# demo_dermis_main_testboard_ibias.net
KiCad netlist of a schematic drawn in Altium Designer
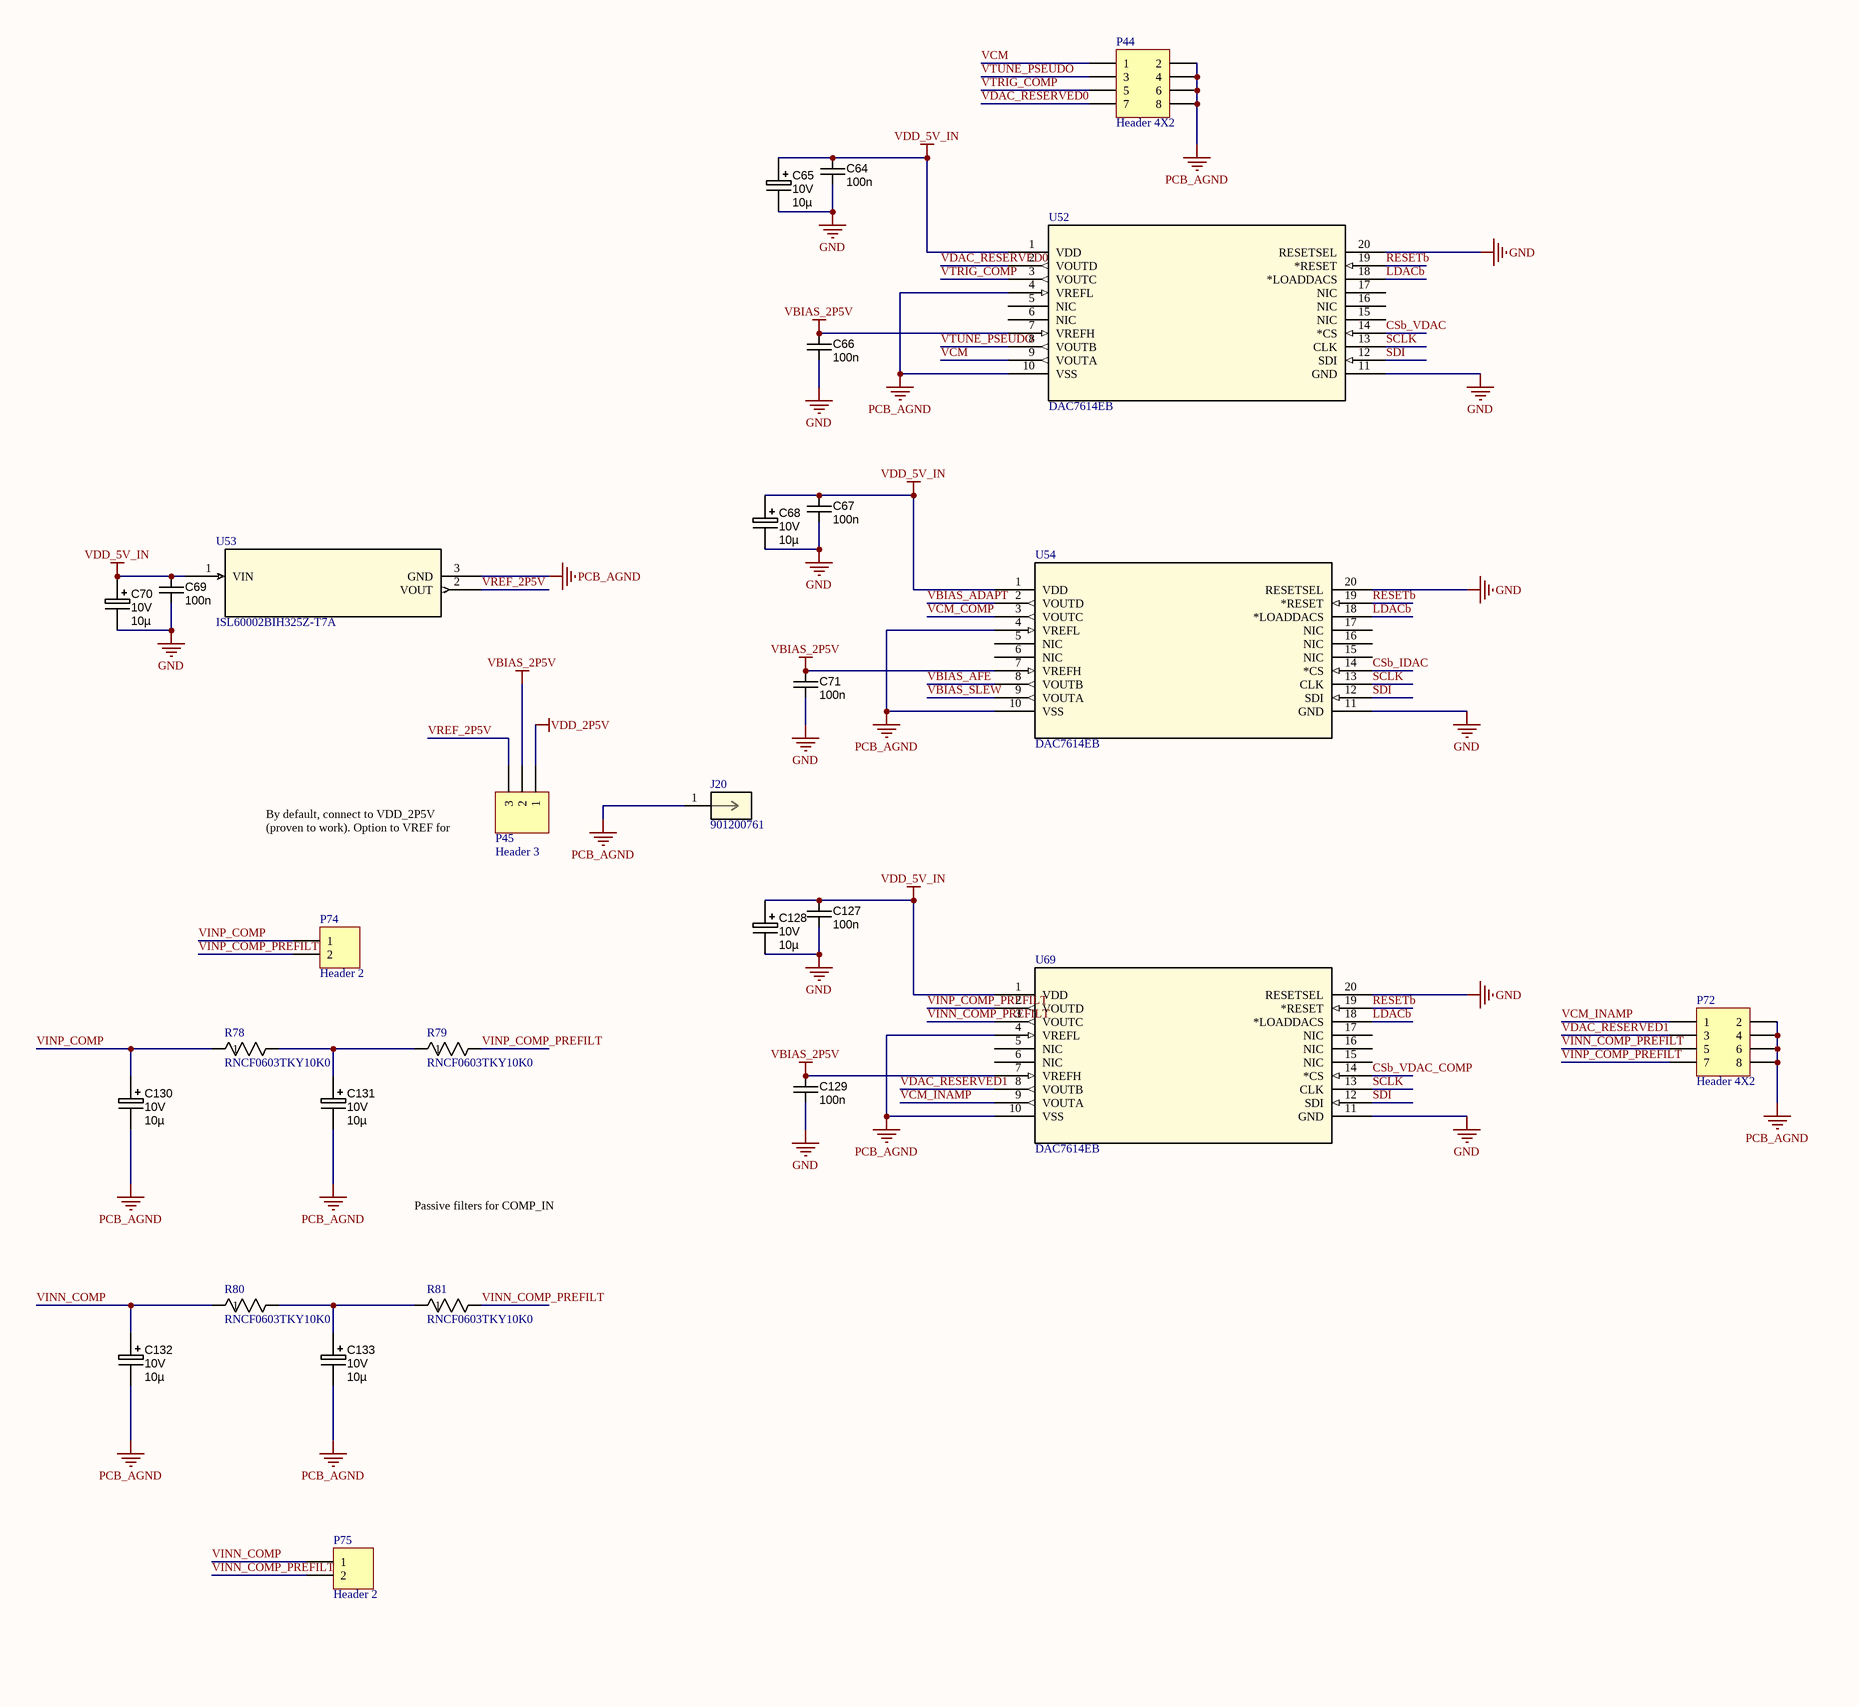
[diagram p0: demo_dermis_main_testboard_ibias.SchDoc, top]
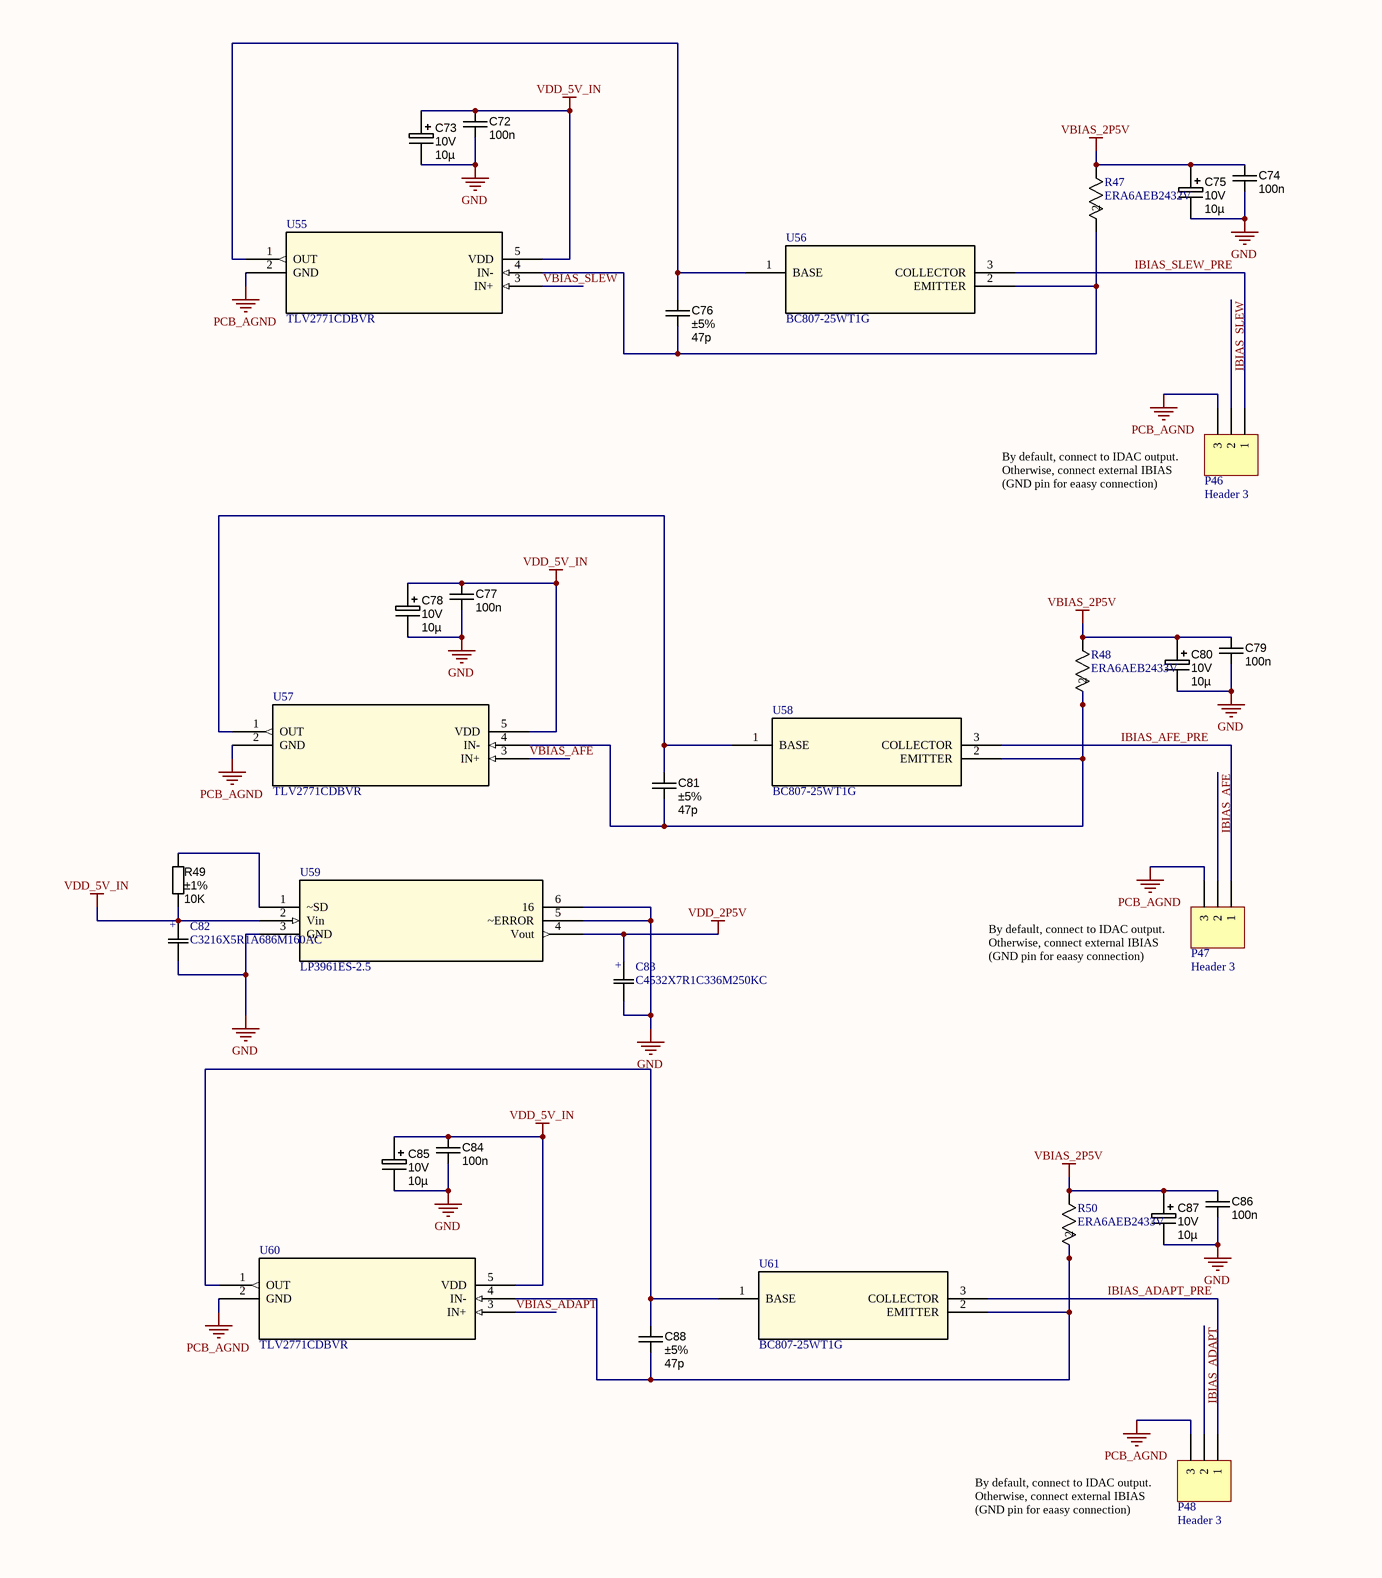
[diagram p1: demo_dermis_main_testboard_ibias.SchDoc, bottom]

(export (version "E")
  (design (tool "Eeschema 10.0.6"))
  (components
    (comp (ref "C64")
      (value "100n")
      (footprint "CAPC1608N")
      (description "Capacitor SMD Cer 100nF 10% 50V X7R 0603")
      (fields (field (name "TOLERANCE") "±10%") (field (name "Comment") "approved sub OK"))
      (libsource (lib "PBL - Capacitors") (part "CAPC_100n_0603"))
    )
    (comp (ref "C65")
      (value "10µ")
      (footprint "CAPMP2012X150USR")
      (description "Capacitor SMD Tantalum 10uF 20% 10V 0805")
      (fields (field (name "TOLERANCE") "±20%") (field (name "RATINGS") "10V"))
      (libsource (lib "PBL - Capacitors") (part "CAPT_10u_0805_10V"))
    )
    (comp (ref "C66")
      (value "100n")
      (footprint "CAPC1608N")
      (description "Capacitor SMD Cer 100nF 10% 50V X7R 0603")
      (fields (field (name "TOLERANCE") "±10%") (field (name "Comment") "approved sub OK"))
      (libsource (lib "PBL - Capacitors") (part "CAPC_100n_0603"))
    )
    (comp (ref "C67")
      (value "100n")
      (footprint "CAPC1608N")
      (description "Capacitor SMD Cer 100nF 10% 50V X7R 0603")
      (fields (field (name "TOLERANCE") "±10%") (field (name "Comment") "approved sub OK"))
      (libsource (lib "PBL - Capacitors") (part "CAPC_100n_0603"))
    )
    (comp (ref "C68")
      (value "10µ")
      (footprint "CAPMP2012X150USR")
      (description "Capacitor SMD Tantalum 10uF 20% 10V 0805")
      (fields (field (name "TOLERANCE") "±20%") (field (name "RATINGS") "10V"))
      (libsource (lib "PBL - Capacitors") (part "CAPT_10u_0805_10V"))
    )
    (comp (ref "C69")
      (value "100n")
      (footprint "CAPC1608N")
      (description "Capacitor SMD Cer 100nF 10% 50V X7R 0603")
      (fields (field (name "TOLERANCE") "±10%") (field (name "Comment") "approved sub OK"))
      (libsource (lib "PBL - Capacitors") (part "CAPC_100n_0603"))
    )
    (comp (ref "C70")
      (value "10µ")
      (footprint "CAPMP2012X150USR")
      (description "Capacitor SMD Tantalum 10uF 20% 10V 0805")
      (fields (field (name "TOLERANCE") "±20%") (field (name "RATINGS") "10V"))
      (libsource (lib "PBL - Capacitors") (part "CAPT_10u_0805_10V"))
    )
    (comp (ref "C71")
      (value "100n")
      (footprint "CAPC1608N")
      (description "Capacitor SMD Cer 100nF 10% 50V X7R 0603")
      (fields (field (name "TOLERANCE") "±10%") (field (name "Comment") "approved sub OK"))
      (libsource (lib "PBL - Capacitors") (part "CAPC_100n_0603"))
    )
    (comp (ref "C72")
      (value "100n")
      (footprint "CAPC1608N")
      (description "Capacitor SMD Cer 100nF 10% 50V X7R 0603")
      (fields (field (name "TOLERANCE") "±10%") (field (name "Comment") "approved sub OK"))
      (libsource (lib "PBL - Capacitors") (part "CAPC_100n_0603"))
    )
    (comp (ref "C73")
      (value "10µ")
      (footprint "CAPMP2012X150USR")
      (description "Capacitor SMD Tantalum 10uF 20% 10V 0805")
      (fields (field (name "TOLERANCE") "±20%") (field (name "RATINGS") "10V"))
      (libsource (lib "PBL - Capacitors") (part "CAPT_10u_0805_10V"))
    )
    (comp (ref "C74")
      (value "100n")
      (footprint "CAPC1608N")
      (description "Capacitor SMD Cer 100nF 10% 50V X7R 0603")
      (fields (field (name "TOLERANCE") "±10%") (field (name "Comment") "approved sub OK"))
      (libsource (lib "PBL - Capacitors") (part "CAPC_100n_0603"))
    )
    (comp (ref "C75")
      (value "10µ")
      (footprint "CAPMP2012X150USR")
      (description "Capacitor SMD Tantalum 10uF 20% 10V 0805")
      (fields (field (name "TOLERANCE") "±20%") (field (name "RATINGS") "10V"))
      (libsource (lib "PBL - Capacitors") (part "CAPT_10u_0805_10V"))
    )
    (comp (ref "C76")
      (value "47p")
      (footprint "CAPC1608N")
      (description "Capacitor SMD Cer 47pF 0603")
      (fields (field (name "TOLERANCE") "±5%"))
      (libsource (lib "MB - Misc") (part "CAPC_47p_0603"))
    )
    (comp (ref "C77")
      (value "100n")
      (footprint "CAPC1608N")
      (description "Capacitor SMD Cer 100nF 10% 50V X7R 0603")
      (fields (field (name "TOLERANCE") "±10%") (field (name "Comment") "approved sub OK"))
      (libsource (lib "PBL - Capacitors") (part "CAPC_100n_0603"))
    )
    (comp (ref "C78")
      (value "10µ")
      (footprint "CAPMP2012X150USR")
      (description "Capacitor SMD Tantalum 10uF 20% 10V 0805")
      (fields (field (name "TOLERANCE") "±20%") (field (name "RATINGS") "10V"))
      (libsource (lib "PBL - Capacitors") (part "CAPT_10u_0805_10V"))
    )
    (comp (ref "C79")
      (value "100n")
      (footprint "CAPC1608N")
      (description "Capacitor SMD Cer 100nF 10% 50V X7R 0603")
      (fields (field (name "TOLERANCE") "±10%") (field (name "Comment") "approved sub OK"))
      (libsource (lib "PBL - Capacitors") (part "CAPC_100n_0603"))
    )
    (comp (ref "C80")
      (value "10µ")
      (footprint "CAPMP2012X150USR")
      (description "Capacitor SMD Tantalum 10uF 20% 10V 0805")
      (fields (field (name "TOLERANCE") "±20%") (field (name "RATINGS") "10V"))
      (libsource (lib "PBL - Capacitors") (part "CAPT_10u_0805_10V"))
    )
    (comp (ref "C81")
      (value "47p")
      (footprint "CAPC1608N")
      (description "Capacitor SMD Cer 47pF 0603")
      (fields (field (name "TOLERANCE") "±5%"))
      (libsource (lib "MB - Misc") (part "CAPC_47p_0603"))
    )
    (comp (ref "C82")
      (value "C3216X5R1A686M160AC")
      (footprint "CAP_3216_TDK")
      (description "No Description Available")
      (fields (field (name "COPYRIGHT") "Copyright (C) 2022 Ultra Librarian. All rights reserved."))
      (libsource (lib "C3216X5R1A686M160AC") (part "C3216X5R1A686M160AC"))
    )
    (comp (ref "C83")
      (value "C4532X7R1C336M250KC")
      (footprint "CAP_4532_TDK")
      (description "No Description Available")
      (fields (field (name "COPYRIGHT") "Copyright (C) 2022 Ultra Librarian. All rights reserved."))
      (libsource (lib "C4532X7R1C336M250KC") (part "C4532X7R1C336M250KC"))
    )
    (comp (ref "C84")
      (value "100n")
      (footprint "CAPC1608N")
      (description "Capacitor SMD Cer 100nF 10% 50V X7R 0603")
      (fields (field (name "TOLERANCE") "±10%") (field (name "Comment") "approved sub OK"))
      (libsource (lib "PBL - Capacitors") (part "CAPC_100n_0603"))
    )
    (comp (ref "C85")
      (value "10µ")
      (footprint "CAPMP2012X150USR")
      (description "Capacitor SMD Tantalum 10uF 20% 10V 0805")
      (fields (field (name "TOLERANCE") "±20%") (field (name "RATINGS") "10V"))
      (libsource (lib "PBL - Capacitors") (part "CAPT_10u_0805_10V"))
    )
    (comp (ref "C86")
      (value "100n")
      (footprint "CAPC1608N")
      (description "Capacitor SMD Cer 100nF 10% 50V X7R 0603")
      (fields (field (name "TOLERANCE") "±10%") (field (name "Comment") "approved sub OK"))
      (libsource (lib "PBL - Capacitors") (part "CAPC_100n_0603"))
    )
    (comp (ref "C87")
      (value "10µ")
      (footprint "CAPMP2012X150USR")
      (description "Capacitor SMD Tantalum 10uF 20% 10V 0805")
      (fields (field (name "TOLERANCE") "±20%") (field (name "RATINGS") "10V"))
      (libsource (lib "PBL - Capacitors") (part "CAPT_10u_0805_10V"))
    )
    (comp (ref "C88")
      (value "47p")
      (footprint "CAPC1608N")
      (description "Capacitor SMD Cer 47pF 0603")
      (fields (field (name "TOLERANCE") "±5%"))
      (libsource (lib "MB - Misc") (part "CAPC_47p_0603"))
    )
    (comp (ref "C127")
      (value "100n")
      (footprint "CAPC1608N")
      (description "Capacitor SMD Cer 100nF 10% 50V X7R 0603")
      (fields (field (name "TOLERANCE") "±10%") (field (name "Comment") "approved sub OK"))
      (libsource (lib "PBL - Capacitors") (part "CAPC_100n_0603"))
    )
    (comp (ref "C128")
      (value "10µ")
      (footprint "CAPMP2012X150USR")
      (description "Capacitor SMD Tantalum 10uF 20% 10V 0805")
      (fields (field (name "TOLERANCE") "±20%") (field (name "RATINGS") "10V"))
      (libsource (lib "PBL - Capacitors") (part "CAPT_10u_0805_10V"))
    )
    (comp (ref "C129")
      (value "100n")
      (footprint "CAPC1608N")
      (description "Capacitor SMD Cer 100nF 10% 50V X7R 0603")
      (fields (field (name "TOLERANCE") "±10%") (field (name "Comment") "approved sub OK"))
      (libsource (lib "PBL - Capacitors") (part "CAPC_100n_0603"))
    )
    (comp (ref "C130")
      (value "10µ")
      (footprint "CAPMP2012X150USR")
      (description "Capacitor SMD Tantalum 10uF 20% 10V 0805")
      (fields (field (name "TOLERANCE") "±20%") (field (name "RATINGS") "10V"))
      (libsource (lib "PBL - Capacitors") (part "CAPT_10u_0805_10V"))
    )
    (comp (ref "C131")
      (value "10µ")
      (footprint "CAPMP2012X150USR")
      (description "Capacitor SMD Tantalum 10uF 20% 10V 0805")
      (fields (field (name "TOLERANCE") "±20%") (field (name "RATINGS") "10V"))
      (libsource (lib "PBL - Capacitors") (part "CAPT_10u_0805_10V"))
    )
    (comp (ref "C132")
      (value "10µ")
      (footprint "CAPMP2012X150USR")
      (description "Capacitor SMD Tantalum 10uF 20% 10V 0805")
      (fields (field (name "TOLERANCE") "±20%") (field (name "RATINGS") "10V"))
      (libsource (lib "PBL - Capacitors") (part "CAPT_10u_0805_10V"))
    )
    (comp (ref "C133")
      (value "10µ")
      (footprint "CAPMP2012X150USR")
      (description "Capacitor SMD Tantalum 10uF 20% 10V 0805")
      (fields (field (name "TOLERANCE") "±20%") (field (name "RATINGS") "10V"))
      (libsource (lib "PBL - Capacitors") (part "CAPT_10u_0805_10V"))
    )
    (comp (ref "J20")
      (value "901200761")
      (footprint "CONN_90120-0761_MOL")
      (description "No Description Available")
      (fields (field (name "COPYRIGHT") "Copyright (C) 2022 Ultra Librarian. All rights reserved."))
      (libsource (lib "901200761") (part "901200761"))
    )
    (comp (ref "P44")
      (value "Header 4X2")
      (footprint "HDR2X4")
      (description "Header, 4-Pin, Dual row")
      (fields (field (name "PUBLISHER") "Altium Limited"))
      (libsource (lib "Miscellaneous Connectors") (part "Header 4X2"))
    )
    (comp (ref "P45")
      (value "Header 3")
      (footprint "HDR1X3")
      (description "Header, 3-Pin")
      (fields (field (name "PUBLISHER") "Altium Limited"))
      (libsource (lib "Miscellaneous Connectors") (part "Header 3"))
    )
    (comp (ref "P46")
      (value "Header 3")
      (footprint "HDR1X3")
      (description "Header, 3-Pin")
      (fields (field (name "PUBLISHER") "Altium Limited"))
      (libsource (lib "Miscellaneous Connectors") (part "Header 3"))
    )
    (comp (ref "P47")
      (value "Header 3")
      (footprint "HDR1X3")
      (description "Header, 3-Pin")
      (fields (field (name "PUBLISHER") "Altium Limited"))
      (libsource (lib "Miscellaneous Connectors") (part "Header 3"))
    )
    (comp (ref "P48")
      (value "Header 3")
      (footprint "HDR1X3")
      (description "Header, 3-Pin")
      (fields (field (name "PUBLISHER") "Altium Limited"))
      (libsource (lib "Miscellaneous Connectors") (part "Header 3"))
    )
    (comp (ref "P72")
      (value "Header 4X2")
      (footprint "HDR2X4")
      (description "Header, 4-Pin, Dual row")
      (fields (field (name "PUBLISHER") "Altium Limited"))
      (libsource (lib "Miscellaneous Connectors") (part "Header 4X2"))
    )
    (comp (ref "P74")
      (value "Header 2")
      (footprint "HDR1X2")
      (description "Header, 2-Pin")
      (fields (field (name "PUBLISHER") "Altium Limited"))
      (libsource (lib "Miscellaneous Connectors") (part "Header 2"))
    )
    (comp (ref "P75")
      (value "Header 2")
      (footprint "HDR1X2")
      (description "Header, 2-Pin")
      (fields (field (name "PUBLISHER") "Altium Limited"))
      (libsource (lib "Miscellaneous Connectors") (part "Header 2"))
    )
    (comp (ref "R47")
      (value "ERA6AEB2432V")
      (footprint "RES_ERA6A_0805_PAN")
      (description "No Description Available")
      (libsource (lib "ERA6AEB2432V") (part "ERA6AEB2432V"))
    )
    (comp (ref "R48")
      (value "ERA6AEB2433V")
      (footprint "RES_ERA6A_0805_PAN")
      (description "No Description Available")
      (libsource (lib "ERA6AEB2433V") (part "ERA6AEB2433V"))
    )
    (comp (ref "R49")
      (value "10K")
      (footprint "RESC1608N")
      (description "Resistor SMD chip 10k Ohm 0.1W 1% 0603")
      (fields (field (name "TOLERANCE") "±1%") (field (name "Comment") "Thick Film"))
      (libsource (lib "analogboard_v2") (part "RES_10K_0603_1%"))
    )
    (comp (ref "R50")
      (value "ERA6AEB2433V")
      (footprint "RES_ERA6A_0805_PAN")
      (description "No Description Available")
      (libsource (lib "ERA6AEB2433V") (part "ERA6AEB2433V"))
    )
    (comp (ref "R78")
      (value "RNCF0603TKY10K0")
      (footprint "STA_RNCF0603_STP")
      (description "No Description Available")
      (libsource (lib "RNCF0603TKY10K0") (part "RNCF0603TKY10K0"))
    )
    (comp (ref "R79")
      (value "RNCF0603TKY10K0")
      (footprint "STA_RNCF0603_STP")
      (description "No Description Available")
      (libsource (lib "RNCF0603TKY10K0") (part "RNCF0603TKY10K0"))
    )
    (comp (ref "R80")
      (value "RNCF0603TKY10K0")
      (footprint "STA_RNCF0603_STP")
      (description "No Description Available")
      (libsource (lib "RNCF0603TKY10K0") (part "RNCF0603TKY10K0"))
    )
    (comp (ref "R81")
      (value "RNCF0603TKY10K0")
      (footprint "STA_RNCF0603_STP")
      (description "No Description Available")
      (libsource (lib "RNCF0603TKY10K0") (part "RNCF0603TKY10K0"))
    )
    (comp (ref "U52")
      (value "DAC7614EB")
      (footprint "DB20")
      (description "No Description Available")
      (fields (field (name "COPYRIGHT") "Copyright (C) 2022 Ultra Librarian. All rights reserved."))
      (libsource (lib "DAC7614EB") (part "DAC7614EB"))
    )
    (comp (ref "U53")
      (value "ISL60002BIH325Z-T7A")
      (footprint "P3_064_INR")
      (description "No Description Available")
      (libsource (lib "ISL60002BIH325Z-T7A") (part "ISL60002BIH325Z-T7A"))
    )
    (comp (ref "U54")
      (value "DAC7614EB")
      (footprint "DB20")
      (description "No Description Available")
      (fields (field (name "COPYRIGHT") "Copyright (C) 2022 Ultra Librarian. All rights reserved."))
      (libsource (lib "DAC7614EB") (part "DAC7614EB"))
    )
    (comp (ref "U55")
      (value "TLV2771CDBVR")
      (footprint "DBV5")
      (description "No Description Available")
      (fields (field (name "COPYRIGHT") "Copyright (C) 2022 Ultra Librarian. All rights reserved."))
      (libsource (lib "TLV2771CDBVR") (part "TLV2771CDBVR"))
    )
    (comp (ref "U56")
      (value "BC807-25WT1G")
      (footprint "SOT-323-3_2P2X1P35_ONS")
      (description "No Description Available")
      (libsource (lib "BC807-25WT1G") (part "BC807-25WT1G"))
    )
    (comp (ref "U57")
      (value "TLV2771CDBVR")
      (footprint "DBV5")
      (description "No Description Available")
      (fields (field (name "COPYRIGHT") "Copyright (C) 2022 Ultra Librarian. All rights reserved."))
      (libsource (lib "TLV2771CDBVR") (part "TLV2771CDBVR"))
    )
    (comp (ref "U58")
      (value "BC807-25WT1G")
      (footprint "SOT-323-3_2P2X1P35_ONS")
      (description "No Description Available")
      (libsource (lib "BC807-25WT1G") (part "BC807-25WT1G"))
    )
    (comp (ref "U59")
      (value "LP3961ES-2.5")
      (footprint "TS5B_TEX")
      (description "No Description Available")
      (fields (field (name "COPYRIGHT") "Copyright (C) 2022 Ultra Librarian. All rights reserved."))
      (libsource (lib "LP3961ES-2P5") (part "LP3961ES-2.5"))
    )
    (comp (ref "U60")
      (value "TLV2771CDBVR")
      (footprint "DBV5")
      (description "No Description Available")
      (fields (field (name "COPYRIGHT") "Copyright (C) 2022 Ultra Librarian. All rights reserved."))
      (libsource (lib "TLV2771CDBVR") (part "TLV2771CDBVR"))
    )
    (comp (ref "U61")
      (value "BC807-25WT1G")
      (footprint "SOT-323-3_2P2X1P35_ONS")
      (description "No Description Available")
      (libsource (lib "BC807-25WT1G") (part "BC807-25WT1G"))
    )
    (comp (ref "U69")
      (value "DAC7614EB")
      (footprint "DB20")
      (description "No Description Available")
      (fields (field (name "COPYRIGHT") "Copyright (C) 2022 Ultra Librarian. All rights reserved."))
      (libsource (lib "DAC7614EB") (part "DAC7614EB"))
    )
  )
  (nets
    (net (code "1") (name "/CSb_IDAC") (class "Default")
      (node (ref "U54") (pin "14") (pinfunction "*CS_14") (pintype "input"))
    )
    (net (code "2") (name "/CSb_VDAC") (class "Default")
      (node (ref "U52") (pin "14") (pinfunction "*CS_14") (pintype "input"))
    )
    (net (code "3") (name "/CSb_VDAC_COMP") (class "Default")
      (node (ref "U69") (pin "14") (pinfunction "*CS_14") (pintype "input"))
    )
    (net (code "4") (name "/IBIAS_ADAPT") (class "Default")
      (node (ref "P48") (pin "2") (pinfunction "2_2") (pintype "passive"))
    )
    (net (code "5") (name "/IBIAS_ADAPT_PRE") (class "Default")
      (node (ref "P48") (pin "1") (pinfunction "1_1") (pintype "passive"))
      (node (ref "U61") (pin "3") (pinfunction "COLLECTOR_3") (pintype "passive"))
    )
    (net (code "6") (name "/IBIAS_AFE") (class "Default")
      (node (ref "P47") (pin "2") (pinfunction "2_2") (pintype "passive"))
    )
    (net (code "7") (name "/IBIAS_AFE_PRE") (class "Default")
      (node (ref "P47") (pin "1") (pinfunction "1_1") (pintype "passive"))
      (node (ref "U58") (pin "3") (pinfunction "COLLECTOR_3") (pintype "passive"))
    )
    (net (code "8") (name "/IBIAS_SLEW") (class "Default")
      (node (ref "P46") (pin "2") (pinfunction "2_2") (pintype "passive"))
    )
    (net (code "9") (name "/IBIAS_SLEW_PRE") (class "Default")
      (node (ref "P46") (pin "1") (pinfunction "1_1") (pintype "passive"))
      (node (ref "U56") (pin "3") (pinfunction "COLLECTOR_3") (pintype "passive"))
    )
    (net (code "10") (name "/LDACb") (class "Default")
      (node (ref "U52") (pin "18") (pinfunction "*LOADDACS_18") (pintype "passive"))
      (node (ref "U54") (pin "18") (pinfunction "*LOADDACS_18") (pintype "passive"))
      (node (ref "U69") (pin "18") (pinfunction "*LOADDACS_18") (pintype "passive"))
    )
    (net (code "11") (name "/RESETb") (class "Default")
      (node (ref "U52") (pin "19") (pinfunction "*RESET_19") (pintype "input"))
      (node (ref "U54") (pin "19") (pinfunction "*RESET_19") (pintype "input"))
      (node (ref "U69") (pin "19") (pinfunction "*RESET_19") (pintype "input"))
    )
    (net (code "12") (name "/SCLK") (class "Default")
      (node (ref "U52") (pin "13") (pinfunction "CLK_13") (pintype "passive"))
      (node (ref "U54") (pin "13") (pinfunction "CLK_13") (pintype "passive"))
      (node (ref "U69") (pin "13") (pinfunction "CLK_13") (pintype "passive"))
    )
    (net (code "13") (name "/SDI") (class "Default")
      (node (ref "U52") (pin "12") (pinfunction "SDI_12") (pintype "input"))
      (node (ref "U54") (pin "12") (pinfunction "SDI_12") (pintype "input"))
      (node (ref "U69") (pin "12") (pinfunction "SDI_12") (pintype "input"))
    )
    (net (code "14") (name "/VBIAS_ADAPT") (class "Default")
      (node (ref "U54") (pin "2") (pinfunction "VOUTD_2") (pintype "output"))
      (node (ref "U60") (pin "3") (pinfunction "IN+_3") (pintype "input"))
    )
    (net (code "15") (name "/VBIAS_AFE") (class "Default")
      (node (ref "U54") (pin "8") (pinfunction "VOUTB_8") (pintype "output"))
      (node (ref "U57") (pin "3") (pinfunction "IN+_3") (pintype "input"))
    )
    (net (code "16") (name "/VBIAS_SLEW") (class "Default")
      (node (ref "U54") (pin "9") (pinfunction "VOUTA_9") (pintype "output"))
      (node (ref "U55") (pin "3") (pinfunction "IN+_3") (pintype "input"))
    )
    (net (code "17") (name "/VCM") (class "Default")
      (node (ref "P44") (pin "1") (pinfunction "1_1") (pintype "passive"))
      (node (ref "U52") (pin "9") (pinfunction "VOUTA_9") (pintype "output"))
    )
    (net (code "18") (name "/VCM_COMP") (class "Default")
      (node (ref "U54") (pin "3") (pinfunction "VOUTC_3") (pintype "output"))
    )
    (net (code "19") (name "/VCM_INAMP") (class "Default")
      (node (ref "P72") (pin "1") (pinfunction "1_1") (pintype "passive"))
      (node (ref "U69") (pin "9") (pinfunction "VOUTA_9") (pintype "output"))
    )
    (net (code "20") (name "/VDAC_RESERVED0") (class "Default")
      (node (ref "P44") (pin "7") (pinfunction "7_7") (pintype "passive"))
      (node (ref "U52") (pin "2") (pinfunction "VOUTD_2") (pintype "output"))
    )
    (net (code "21") (name "/VDAC_RESERVED1") (class "Default")
      (node (ref "P72") (pin "3") (pinfunction "3_3") (pintype "passive"))
      (node (ref "U69") (pin "8") (pinfunction "VOUTB_8") (pintype "output"))
    )
    (net (code "22") (name "/VINN_COMP") (class "Default")
      (node (ref "C132") (pin "1") (pintype "passive"))
      (node (ref "P75") (pin "1") (pinfunction "1_1") (pintype "passive"))
      (node (ref "R80") (pin "1") (pinfunction "1_1") (pintype "passive"))
    )
    (net (code "23") (name "/VINN_COMP_PREFILT") (class "Default")
      (node (ref "P72") (pin "5") (pinfunction "5_5") (pintype "passive"))
      (node (ref "P75") (pin "2") (pinfunction "2_2") (pintype "passive"))
      (node (ref "R81") (pin "2") (pinfunction "2_2") (pintype "passive"))
      (node (ref "U69") (pin "3") (pinfunction "VOUTC_3") (pintype "output"))
    )
    (net (code "24") (name "/VINP_COMP") (class "Default")
      (node (ref "C130") (pin "1") (pintype "passive"))
      (node (ref "P74") (pin "1") (pinfunction "1_1") (pintype "passive"))
      (node (ref "R78") (pin "1") (pinfunction "1_1") (pintype "passive"))
    )
    (net (code "25") (name "/VINP_COMP_PREFILT") (class "Default")
      (node (ref "P72") (pin "7") (pinfunction "7_7") (pintype "passive"))
      (node (ref "P74") (pin "2") (pinfunction "2_2") (pintype "passive"))
      (node (ref "R79") (pin "2") (pinfunction "2_2") (pintype "passive"))
      (node (ref "U69") (pin "2") (pinfunction "VOUTD_2") (pintype "output"))
    )
    (net (code "26") (name "/VREF_2P5V") (class "Default")
      (node (ref "P45") (pin "3") (pinfunction "3_3") (pintype "passive"))
      (node (ref "U53") (pin "2") (pinfunction "VOUT_2") (pintype "output"))
    )
    (net (code "27") (name "/VTRIG_COMP") (class "Default")
      (node (ref "P44") (pin "5") (pinfunction "5_5") (pintype "passive"))
      (node (ref "U52") (pin "3") (pinfunction "VOUTC_3") (pintype "output"))
    )
    (net (code "28") (name "/VTUNE_PSEUDO") (class "Default")
      (node (ref "P44") (pin "3") (pinfunction "3_3") (pintype "passive"))
      (node (ref "U52") (pin "8") (pinfunction "VOUTB_8") (pintype "output"))
    )
    (net (code "29") (name "GND") (class "Default")
      (node (ref "C127") (pin "2") (pintype "passive"))
      (node (ref "C128") (pin "2") (pintype "passive"))
      (node (ref "C129") (pin "2") (pintype "passive"))
      (node (ref "C64") (pin "2") (pintype "passive"))
      (node (ref "C65") (pin "2") (pintype "passive"))
      (node (ref "C66") (pin "2") (pintype "passive"))
      (node (ref "C67") (pin "2") (pintype "passive"))
      (node (ref "C68") (pin "2") (pintype "passive"))
      (node (ref "C69") (pin "2") (pintype "passive"))
      (node (ref "C70") (pin "2") (pintype "passive"))
      (node (ref "C71") (pin "2") (pintype "passive"))
      (node (ref "C72") (pin "2") (pintype "passive"))
      (node (ref "C73") (pin "2") (pintype "passive"))
      (node (ref "C74") (pin "2") (pintype "passive"))
      (node (ref "C75") (pin "2") (pintype "passive"))
      (node (ref "C77") (pin "2") (pintype "passive"))
      (node (ref "C78") (pin "2") (pintype "passive"))
      (node (ref "C79") (pin "2") (pintype "passive"))
      (node (ref "C80") (pin "2") (pintype "passive"))
      (node (ref "C82") (pin "2") (pinfunction "2_2") (pintype "passive"))
      (node (ref "C83") (pin "2") (pinfunction "2_2") (pintype "passive"))
      (node (ref "C84") (pin "2") (pintype "passive"))
      (node (ref "C85") (pin "2") (pintype "passive"))
      (node (ref "C86") (pin "2") (pintype "passive"))
      (node (ref "C87") (pin "2") (pintype "passive"))
      (node (ref "U52") (pin "11") (pinfunction "GND_11") (pintype "power_in"))
      (node (ref "U52") (pin "20") (pinfunction "RESETSEL_20") (pintype "passive"))
      (node (ref "U54") (pin "11") (pinfunction "GND_11") (pintype "power_in"))
      (node (ref "U54") (pin "20") (pinfunction "RESETSEL_20") (pintype "passive"))
      (node (ref "U59") (pin "3") (pinfunction "GND_3") (pintype "passive"))
      (node (ref "U59") (pin "5") (pinfunction "~ERROR_5") (pintype "passive"))
      (node (ref "U59") (pin "6") (pinfunction "16_6") (pintype "passive"))
      (node (ref "U69") (pin "11") (pinfunction "GND_11") (pintype "power_in"))
      (node (ref "U69") (pin "20") (pinfunction "RESETSEL_20") (pintype "passive"))
    )
    (net (code "30") (name "Net-(C131-Pad1)") (class "Default")
      (node (ref "C131") (pin "1") (pintype "passive"))
      (node (ref "R78") (pin "2") (pinfunction "2_2") (pintype "passive"))
      (node (ref "R79") (pin "1") (pinfunction "1_1") (pintype "passive"))
    )
    (net (code "31") (name "Net-(C133-Pad1)") (class "Default")
      (node (ref "C133") (pin "1") (pintype "passive"))
      (node (ref "R80") (pin "2") (pinfunction "2_2") (pintype "passive"))
      (node (ref "R81") (pin "1") (pinfunction "1_1") (pintype "passive"))
    )
    (net (code "32") (name "Net-(U55-IN-)") (class "Default")
      (node (ref "C76") (pin "1") (pintype "passive"))
      (node (ref "R47") (pin "2") (pinfunction "2_2") (pintype "passive"))
      (node (ref "U55") (pin "4") (pinfunction "IN-_4") (pintype "input"))
      (node (ref "U56") (pin "2") (pinfunction "EMITTER_2") (pintype "passive"))
    )
    (net (code "33") (name "Net-(U55-OUT)") (class "Default")
      (node (ref "C76") (pin "2") (pintype "passive"))
      (node (ref "U55") (pin "1") (pinfunction "OUT_1") (pintype "output"))
      (node (ref "U56") (pin "1") (pinfunction "BASE_1") (pintype "passive"))
    )
    (net (code "34") (name "Net-(U57-IN-)") (class "Default")
      (node (ref "C81") (pin "1") (pintype "passive"))
      (node (ref "R48") (pin "2") (pinfunction "2_2") (pintype "passive"))
      (node (ref "U57") (pin "4") (pinfunction "IN-_4") (pintype "input"))
      (node (ref "U58") (pin "2") (pinfunction "EMITTER_2") (pintype "passive"))
    )
    (net (code "35") (name "Net-(U57-OUT)") (class "Default")
      (node (ref "C81") (pin "2") (pintype "passive"))
      (node (ref "U57") (pin "1") (pinfunction "OUT_1") (pintype "output"))
      (node (ref "U58") (pin "1") (pinfunction "BASE_1") (pintype "passive"))
    )
    (net (code "36") (name "Net-(U59-~SD)") (class "Default")
      (node (ref "R49") (pin "1") (pinfunction "1_1") (pintype "passive"))
      (node (ref "U59") (pin "1") (pinfunction "~SD_1") (pintype "passive"))
    )
    (net (code "37") (name "Net-(U60-IN-)") (class "Default")
      (node (ref "C88") (pin "1") (pintype "passive"))
      (node (ref "R50") (pin "2") (pinfunction "2_2") (pintype "passive"))
      (node (ref "U60") (pin "4") (pinfunction "IN-_4") (pintype "input"))
      (node (ref "U61") (pin "2") (pinfunction "EMITTER_2") (pintype "passive"))
    )
    (net (code "38") (name "Net-(U60-OUT)") (class "Default")
      (node (ref "C88") (pin "2") (pintype "passive"))
      (node (ref "U60") (pin "1") (pinfunction "OUT_1") (pintype "output"))
      (node (ref "U61") (pin "1") (pinfunction "BASE_1") (pintype "passive"))
    )
    (net (code "39") (name "PCB_AGND") (class "Default")
      (node (ref "C130") (pin "2") (pintype "passive"))
      (node (ref "C131") (pin "2") (pintype "passive"))
      (node (ref "C132") (pin "2") (pintype "passive"))
      (node (ref "C133") (pin "2") (pintype "passive"))
      (node (ref "J20") (pin "1") (pinfunction "1_1") (pintype "passive"))
      (node (ref "P44") (pin "2") (pinfunction "2_2") (pintype "passive"))
      (node (ref "P44") (pin "4") (pinfunction "4_4") (pintype "passive"))
      (node (ref "P44") (pin "6") (pinfunction "6_6") (pintype "passive"))
      (node (ref "P44") (pin "8") (pinfunction "8_8") (pintype "passive"))
      (node (ref "P46") (pin "3") (pinfunction "3_3") (pintype "passive"))
      (node (ref "P47") (pin "3") (pinfunction "3_3") (pintype "passive"))
      (node (ref "P48") (pin "3") (pinfunction "3_3") (pintype "passive"))
      (node (ref "P72") (pin "2") (pinfunction "2_2") (pintype "passive"))
      (node (ref "P72") (pin "4") (pinfunction "4_4") (pintype "passive"))
      (node (ref "P72") (pin "6") (pinfunction "6_6") (pintype "passive"))
      (node (ref "P72") (pin "8") (pinfunction "8_8") (pintype "passive"))
      (node (ref "U52") (pin "10") (pinfunction "VSS_10") (pintype "power_in"))
      (node (ref "U52") (pin "4") (pinfunction "VREFL_4") (pintype "input"))
      (node (ref "U53") (pin "3") (pinfunction "GND_3") (pintype "power_in"))
      (node (ref "U54") (pin "10") (pinfunction "VSS_10") (pintype "power_in"))
      (node (ref "U54") (pin "4") (pinfunction "VREFL_4") (pintype "input"))
      (node (ref "U55") (pin "2") (pinfunction "GND_2") (pintype "power_in"))
      (node (ref "U57") (pin "2") (pinfunction "GND_2") (pintype "power_in"))
      (node (ref "U60") (pin "2") (pinfunction "GND_2") (pintype "power_in"))
      (node (ref "U69") (pin "10") (pinfunction "VSS_10") (pintype "power_in"))
      (node (ref "U69") (pin "4") (pinfunction "VREFL_4") (pintype "input"))
    )
    (net (code "40") (name "VBIAS_2P5V") (class "Default")
      (node (ref "C129") (pin "1") (pintype "passive"))
      (node (ref "C66") (pin "1") (pintype "passive"))
      (node (ref "C71") (pin "1") (pintype "passive"))
      (node (ref "C74") (pin "1") (pintype "passive"))
      (node (ref "C75") (pin "1") (pintype "passive"))
      (node (ref "C79") (pin "1") (pintype "passive"))
      (node (ref "C80") (pin "1") (pintype "passive"))
      (node (ref "C86") (pin "1") (pintype "passive"))
      (node (ref "C87") (pin "1") (pintype "passive"))
      (node (ref "P45") (pin "2") (pinfunction "2_2") (pintype "passive"))
      (node (ref "R47") (pin "1") (pinfunction "1_1") (pintype "passive"))
      (node (ref "R48") (pin "1") (pinfunction "1_1") (pintype "passive"))
      (node (ref "R50") (pin "1") (pinfunction "1_1") (pintype "passive"))
      (node (ref "U52") (pin "7") (pinfunction "VREFH_7") (pintype "input"))
      (node (ref "U54") (pin "7") (pinfunction "VREFH_7") (pintype "input"))
      (node (ref "U69") (pin "7") (pinfunction "VREFH_7") (pintype "input"))
    )
    (net (code "41") (name "VDD_2P5V") (class "Default")
      (node (ref "C83") (pin "1") (pinfunction "1_1") (pintype "passive"))
      (node (ref "P45") (pin "1") (pinfunction "1_1") (pintype "passive"))
      (node (ref "U59") (pin "4") (pinfunction "Vout_4") (pintype "output"))
    )
    (net (code "42") (name "VDD_5V_IN") (class "Default")
      (node (ref "C127") (pin "1") (pintype "passive"))
      (node (ref "C128") (pin "1") (pintype "passive"))
      (node (ref "C64") (pin "1") (pintype "passive"))
      (node (ref "C65") (pin "1") (pintype "passive"))
      (node (ref "C67") (pin "1") (pintype "passive"))
      (node (ref "C68") (pin "1") (pintype "passive"))
      (node (ref "C69") (pin "1") (pintype "passive"))
      (node (ref "C70") (pin "1") (pintype "passive"))
      (node (ref "C72") (pin "1") (pintype "passive"))
      (node (ref "C73") (pin "1") (pintype "passive"))
      (node (ref "C77") (pin "1") (pintype "passive"))
      (node (ref "C78") (pin "1") (pintype "passive"))
      (node (ref "C82") (pin "1") (pinfunction "1_1") (pintype "passive"))
      (node (ref "C84") (pin "1") (pintype "passive"))
      (node (ref "C85") (pin "1") (pintype "passive"))
      (node (ref "R49") (pin "2") (pinfunction "2_2") (pintype "passive"))
      (node (ref "U52") (pin "1") (pinfunction "VDD_1") (pintype "power_in"))
      (node (ref "U53") (pin "1") (pinfunction "VIN_1") (pintype "input"))
      (node (ref "U54") (pin "1") (pinfunction "VDD_1") (pintype "power_in"))
      (node (ref "U55") (pin "5") (pinfunction "VDD_5") (pintype "power_in"))
      (node (ref "U57") (pin "5") (pinfunction "VDD_5") (pintype "power_in"))
      (node (ref "U59") (pin "2") (pinfunction "Vin_2") (pintype "input"))
      (node (ref "U60") (pin "5") (pinfunction "VDD_5") (pintype "power_in"))
      (node (ref "U69") (pin "1") (pinfunction "VDD_1") (pintype "power_in"))
    )
    (net (code "43") (name "unconnected-(U52-NIC-Pad5)") (class "Default")
      (node (ref "U52") (pin "5") (pinfunction "NIC_5") (pintype "passive"))
    )
    (net (code "44") (name "unconnected-(U52-NIC-Pad6)") (class "Default")
      (node (ref "U52") (pin "6") (pinfunction "NIC_6") (pintype "passive"))
    )
    (net (code "45") (name "unconnected-(U52-NIC-Pad15)") (class "Default")
      (node (ref "U52") (pin "15") (pinfunction "NIC_15") (pintype "passive"))
    )
    (net (code "46") (name "unconnected-(U52-NIC-Pad16)") (class "Default")
      (node (ref "U52") (pin "16") (pinfunction "NIC_16") (pintype "passive"))
    )
    (net (code "47") (name "unconnected-(U52-NIC-Pad17)") (class "Default")
      (node (ref "U52") (pin "17") (pinfunction "NIC_17") (pintype "passive"))
    )
    (net (code "48") (name "unconnected-(U54-NIC-Pad5)") (class "Default")
      (node (ref "U54") (pin "5") (pinfunction "NIC_5") (pintype "passive"))
    )
    (net (code "49") (name "unconnected-(U54-NIC-Pad6)") (class "Default")
      (node (ref "U54") (pin "6") (pinfunction "NIC_6") (pintype "passive"))
    )
    (net (code "50") (name "unconnected-(U54-NIC-Pad15)") (class "Default")
      (node (ref "U54") (pin "15") (pinfunction "NIC_15") (pintype "passive"))
    )
    (net (code "51") (name "unconnected-(U54-NIC-Pad16)") (class "Default")
      (node (ref "U54") (pin "16") (pinfunction "NIC_16") (pintype "passive"))
    )
    (net (code "52") (name "unconnected-(U54-NIC-Pad17)") (class "Default")
      (node (ref "U54") (pin "17") (pinfunction "NIC_17") (pintype "passive"))
    )
    (net (code "53") (name "unconnected-(U69-NIC-Pad5)") (class "Default")
      (node (ref "U69") (pin "5") (pinfunction "NIC_5") (pintype "passive"))
    )
    (net (code "54") (name "unconnected-(U69-NIC-Pad6)") (class "Default")
      (node (ref "U69") (pin "6") (pinfunction "NIC_6") (pintype "passive"))
    )
    (net (code "55") (name "unconnected-(U69-NIC-Pad15)") (class "Default")
      (node (ref "U69") (pin "15") (pinfunction "NIC_15") (pintype "passive"))
    )
    (net (code "56") (name "unconnected-(U69-NIC-Pad16)") (class "Default")
      (node (ref "U69") (pin "16") (pinfunction "NIC_16") (pintype "passive"))
    )
    (net (code "57") (name "unconnected-(U69-NIC-Pad17)") (class "Default")
      (node (ref "U69") (pin "17") (pinfunction "NIC_17") (pintype "passive"))
    )
  )
)
